# pressure.net
KiCad netlist of a schematic drawn in Altium Designer
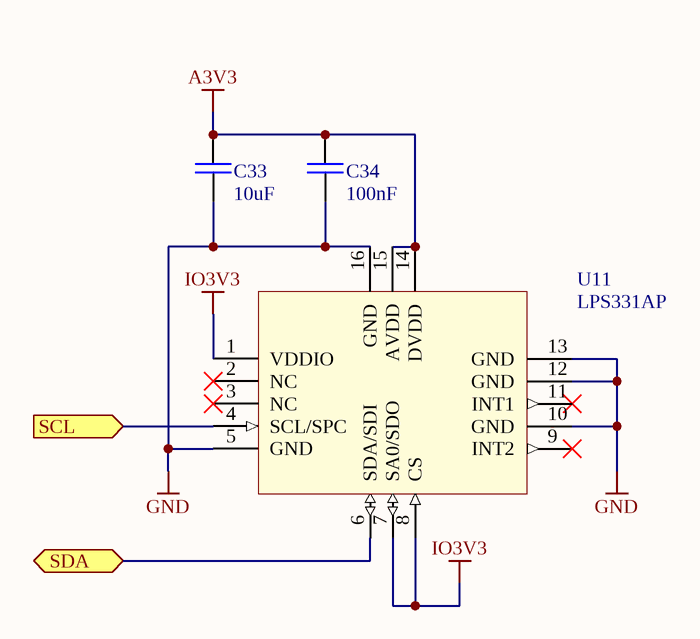
[diagram p0: pressure.SchDoc]

(export (version "E")
  (design (tool "Eeschema 10.0.6"))
  (components
    (comp (ref "C33")
      (value "10uF")
      (footprint "0805")
      (description "Capacitor")
      (fields (field (name "OWNER") "Nuno Brum"))
      (libsource (lib "Alcetronics_Devices") (part "CAP"))
    )
    (comp (ref "C34")
      (value "100nF")
      (footprint "0603")
      (description "Capacitor")
      (fields (field (name "OWNER") "Nuno Brum"))
      (libsource (lib "Alcetronics_Devices") (part "CAP"))
    )
    (comp (ref "U11")
      (value "LPS331AP")
      (footprint "HCLGA-16")
      (description "Pressure sensor, 260 - 1260 mbar")
      (libsource (lib "Alcetronics_IC") (part "LPS331AP"))
    )
  )
  (nets
    (net (code "1") (name "/SCL") (class "Default")
      (node (ref "U11") (pin "4") (pinfunction "SCL/SPC_4") (pintype "input"))
    )
    (net (code "2") (name "/SDA") (class "Default")
      (node (ref "U11") (pin "6") (pinfunction "SDA/SDI_6") (pintype "bidirectional"))
    )
    (net (code "3") (name "A3V3") (class "Default")
      (node (ref "C33") (pin "2") (pinfunction "2_2") (pintype "passive"))
      (node (ref "C34") (pin "2") (pinfunction "2_2") (pintype "passive"))
      (node (ref "U11") (pin "14") (pinfunction "DVDD_14") (pintype "power_in"))
      (node (ref "U11") (pin "15") (pinfunction "AVDD_15") (pintype "power_in"))
    )
    (net (code "4") (name "GND") (class "Default")
      (node (ref "C33") (pin "1") (pinfunction "1_1") (pintype "passive"))
      (node (ref "C34") (pin "1") (pinfunction "1_1") (pintype "passive"))
      (node (ref "U11") (pin "10") (pinfunction "GND_10") (pintype "power_in"))
      (node (ref "U11") (pin "12") (pinfunction "GND_12") (pintype "power_in"))
      (node (ref "U11") (pin "13") (pinfunction "GND_13") (pintype "power_in"))
      (node (ref "U11") (pin "16") (pinfunction "GND_16") (pintype "power_in"))
      (node (ref "U11") (pin "5") (pinfunction "GND_5") (pintype "power_in"))
    )
    (net (code "5") (name "IO3V3") (class "Default")
      (node (ref "U11") (pin "1") (pinfunction "VDDIO_1") (pintype "power_in"))
      (node (ref "U11") (pin "7") (pinfunction "SA0/SDO_7") (pintype "bidirectional"))
      (node (ref "U11") (pin "8") (pinfunction "CS_8") (pintype "input"))
    )
    (net (code "6") (name "unconnected-(U11-INT1-Pad11)") (class "Default")
      (node (ref "U11") (pin "11") (pinfunction "INT1_11") (pintype "output+no_connect"))
    )
    (net (code "7") (name "unconnected-(U11-INT2-Pad9)") (class "Default")
      (node (ref "U11") (pin "9") (pinfunction "INT2_9") (pintype "output+no_connect"))
    )
    (net (code "8") (name "unconnected-(U11-NC-Pad2)") (class "Default")
      (node (ref "U11") (pin "2") (pinfunction "NC_2") (pintype "passive+no_connect"))
    )
    (net (code "9") (name "unconnected-(U11-NC-Pad3)") (class "Default")
      (node (ref "U11") (pin "3") (pinfunction "NC_3") (pintype "passive+no_connect"))
    )
  )
)
